# newbutton.net
KiCad netlist of a schematic drawn in EAGLE
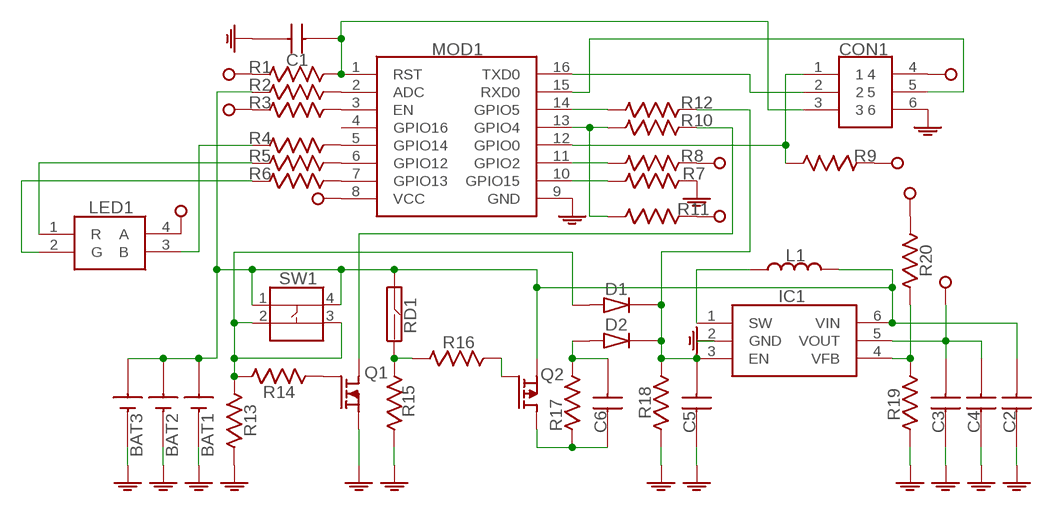
[diagram p0: schematic, sheet 1]

(export (version "E")
  (design (tool "Eeschema 10.0.6"))
  (components
    (comp (ref "BAT1")
      (value "AAA-CONTACTS")
      (footprint "eagle-import:AAA-CONTACTS")
      (libsource (lib "eagle-import") (part "AAA-CONTACTS"))
    )
    (comp (ref "BAT2")
      (value "AAA-CONTACTS")
      (footprint "eagle-import:AAA-CONTACTS")
      (libsource (lib "eagle-import") (part "AAA-CONTACTS"))
    )
    (comp (ref "BAT3")
      (value "AAA-CONTACTS")
      (footprint "eagle-import:AAA-CONTACTS")
      (libsource (lib "eagle-import") (part "AAA-CONTACTS"))
    )
    (comp (ref "C1")
      (value "CAPACITOR-0603")
      (footprint "eagle-import:0603")
      (libsource (lib "eagle-import") (part "CAPACITOR-0603"))
    )
    (comp (ref "C2")
      (value "CAPACITOR-0805")
      (footprint "eagle-import:0805")
      (libsource (lib "eagle-import") (part "CAPACITOR-0805"))
    )
    (comp (ref "C3")
      (value "CAPACITOR-0805")
      (footprint "eagle-import:0805")
      (libsource (lib "eagle-import") (part "CAPACITOR-0805"))
    )
    (comp (ref "C4")
      (value "CAPACITOR-0603")
      (footprint "eagle-import:0603")
      (libsource (lib "eagle-import") (part "CAPACITOR-0603"))
    )
    (comp (ref "C5")
      (value "CAPACITOR-0603")
      (footprint "eagle-import:0603")
      (libsource (lib "eagle-import") (part "CAPACITOR-0603"))
    )
    (comp (ref "C6")
      (value "CAPACITOR-0603")
      (footprint "eagle-import:0603")
      (libsource (lib "eagle-import") (part "CAPACITOR-0603"))
    )
    (comp (ref "CON1")
      (value "HEADER-6P-2R-DIP-2_54MM")
      (footprint "eagle-import:HEADER-6P-2R-DIP-2_54MM")
      (libsource (lib "eagle-import") (part "HEADER-6P-2R-DIP-2_54MM"))
    )
    (comp (ref "D1")
      (value "DIODE-0603")
      (footprint "eagle-import:0603-DIODE")
      (libsource (lib "eagle-import") (part "DIODE-0603"))
    )
    (comp (ref "D2")
      (value "DIODE-0603")
      (footprint "eagle-import:0603-DIODE")
      (libsource (lib "eagle-import") (part "DIODE-0603"))
    )
    (comp (ref "IC1")
      (value "MCP1640")
      (footprint "eagle-import:SOT23-6")
      (libsource (lib "eagle-import") (part "MCP1640"))
    )
    (comp (ref "L1")
      (value "INDUCTOR-0520-0630")
      (footprint "eagle-import:INDUCTOR-0520-0630")
      (libsource (lib "eagle-import") (part "INDUCTOR-0520-0630"))
    )
    (comp (ref "LED1")
      (value "LED-RGB-3528-PLCC4")
      (footprint "eagle-import:LED-RGB-3528-PLCC4")
      (libsource (lib "eagle-import") (part "LED-RGB-3528-PLCC4"))
    )
    (comp (ref "MOD1")
      (value "ESP-12S")
      (footprint "eagle-import:ESP-12S")
      (libsource (lib "eagle-import") (part "ESP-12S"))
    )
    (comp (ref "Q1")
      (value "N-MOSFET")
      (footprint "eagle-import:SOT23-3")
      (libsource (lib "eagle-import") (part "N-MOSFET"))
    )
    (comp (ref "Q2")
      (value "P-MOSFET")
      (footprint "eagle-import:SOT23-3")
      (libsource (lib "eagle-import") (part "P-MOSFET"))
    )
    (comp (ref "R1")
      (value "RESISTOR-0603")
      (footprint "eagle-import:0603")
      (libsource (lib "eagle-import") (part "RESISTOR-0603"))
    )
    (comp (ref "R2")
      (value "RESISTOR-0603")
      (footprint "eagle-import:0603")
      (libsource (lib "eagle-import") (part "RESISTOR-0603"))
    )
    (comp (ref "R3")
      (value "RESISTOR-0603")
      (footprint "eagle-import:0603")
      (libsource (lib "eagle-import") (part "RESISTOR-0603"))
    )
    (comp (ref "R4")
      (value "RESISTOR-0603")
      (footprint "eagle-import:0603")
      (libsource (lib "eagle-import") (part "RESISTOR-0603"))
    )
    (comp (ref "R5")
      (value "RESISTOR-0603")
      (footprint "eagle-import:0603")
      (libsource (lib "eagle-import") (part "RESISTOR-0603"))
    )
    (comp (ref "R6")
      (value "RESISTOR-0603")
      (footprint "eagle-import:0603")
      (libsource (lib "eagle-import") (part "RESISTOR-0603"))
    )
    (comp (ref "R7")
      (value "RESISTOR-0603")
      (footprint "eagle-import:0603")
      (libsource (lib "eagle-import") (part "RESISTOR-0603"))
    )
    (comp (ref "R8")
      (value "RESISTOR-0603")
      (footprint "eagle-import:0603")
      (libsource (lib "eagle-import") (part "RESISTOR-0603"))
    )
    (comp (ref "R9")
      (value "RESISTOR-0603")
      (footprint "eagle-import:0603")
      (libsource (lib "eagle-import") (part "RESISTOR-0603"))
    )
    (comp (ref "R10")
      (value "RESISTOR-0603")
      (footprint "eagle-import:0603")
      (libsource (lib "eagle-import") (part "RESISTOR-0603"))
    )
    (comp (ref "R11")
      (value "RESISTOR-0603")
      (footprint "eagle-import:0603")
      (libsource (lib "eagle-import") (part "RESISTOR-0603"))
    )
    (comp (ref "R12")
      (value "RESISTOR-0603")
      (footprint "eagle-import:0603")
      (libsource (lib "eagle-import") (part "RESISTOR-0603"))
    )
    (comp (ref "R13")
      (value "RESISTOR-0603")
      (footprint "eagle-import:0603")
      (libsource (lib "eagle-import") (part "RESISTOR-0603"))
    )
    (comp (ref "R14")
      (value "RESISTOR-0603")
      (footprint "eagle-import:0603")
      (libsource (lib "eagle-import") (part "RESISTOR-0603"))
    )
    (comp (ref "R15")
      (value "RESISTOR-0603")
      (footprint "eagle-import:0603")
      (libsource (lib "eagle-import") (part "RESISTOR-0603"))
    )
    (comp (ref "R16")
      (value "RESISTOR-0603")
      (footprint "eagle-import:0603")
      (libsource (lib "eagle-import") (part "RESISTOR-0603"))
    )
    (comp (ref "R17")
      (value "RESISTOR-0603")
      (footprint "eagle-import:0603")
      (libsource (lib "eagle-import") (part "RESISTOR-0603"))
    )
    (comp (ref "R18")
      (value "RESISTOR-0603")
      (footprint "eagle-import:0603")
      (libsource (lib "eagle-import") (part "RESISTOR-0603"))
    )
    (comp (ref "R19")
      (value "RESISTOR-0603")
      (footprint "eagle-import:0603")
      (libsource (lib "eagle-import") (part "RESISTOR-0603"))
    )
    (comp (ref "R20")
      (value "RESISTOR-0603")
      (footprint "eagle-import:0603")
      (libsource (lib "eagle-import") (part "RESISTOR-0603"))
    )
    (comp (ref "RD1")
      (value "REED-DIP")
      (footprint "eagle-import:REED-DIP")
      (libsource (lib "eagle-import") (part "REED-DIP"))
    )
    (comp (ref "SW1")
      (value "BUTTON-4P-SMD-5X5")
      (footprint "eagle-import:BUTTON-4P-SMD-5X5")
      (libsource (lib "eagle-import") (part "BUTTON-4P-SMD-5X5"))
    )
  )
  (nets
    (net (code "1") (name "GND") (class "Default")
      (node (ref "BAT1") (pin "2") (pinfunction "-_2") (pintype "power_in"))
      (node (ref "BAT1") (pin "4") (pinfunction "-_4") (pintype "power_in"))
      (node (ref "BAT2") (pin "2") (pinfunction "-_2") (pintype "power_in"))
      (node (ref "BAT2") (pin "4") (pinfunction "-_4") (pintype "power_in"))
      (node (ref "BAT3") (pin "2") (pinfunction "-_2") (pintype "power_in"))
      (node (ref "BAT3") (pin "4") (pinfunction "-_4") (pintype "power_in"))
      (node (ref "C1") (pin "1") (pinfunction "1_1") (pintype "passive"))
      (node (ref "C2") (pin "1") (pinfunction "1_1") (pintype "passive"))
      (node (ref "C3") (pin "1") (pinfunction "1_1") (pintype "passive"))
      (node (ref "C4") (pin "1") (pinfunction "1_1") (pintype "passive"))
      (node (ref "C5") (pin "1") (pinfunction "1_1") (pintype "passive"))
      (node (ref "CON1") (pin "6") (pinfunction "6_6") (pintype "bidirectional"))
      (node (ref "IC1") (pin "2") (pinfunction "GND_2") (pintype "power_in"))
      (node (ref "MOD1") (pin "9") (pinfunction "GND_9") (pintype "bidirectional"))
      (node (ref "Q1") (pin "2") (pinfunction "S_2") (pintype "bidirectional"))
      (node (ref "R13") (pin "1") (pinfunction "1_1") (pintype "passive"))
      (node (ref "R15") (pin "1") (pinfunction "1_1") (pintype "passive"))
      (node (ref "R18") (pin "1") (pinfunction "1_1") (pintype "passive"))
      (node (ref "R19") (pin "1") (pinfunction "1_1") (pintype "passive"))
      (node (ref "R7") (pin "2") (pinfunction "2_2") (pintype "passive"))
    )
    (net (code "2") (name "Net-(D1-A)") (class "Default")
      (node (ref "D1") (pin "1") (pinfunction "A_1") (pintype "bidirectional"))
      (node (ref "R13") (pin "2") (pinfunction "2_2") (pintype "passive"))
      (node (ref "R14") (pin "1") (pinfunction "1_1") (pintype "passive"))
      (node (ref "SW1") (pin "2") (pinfunction "2_2") (pintype "passive"))
      (node (ref "SW1") (pin "3") (pinfunction "3_3") (pintype "passive"))
    )
    (net (code "3") (name "Net-(D1-K)") (class "Default")
      (node (ref "C5") (pin "2") (pinfunction "2_2") (pintype "passive"))
      (node (ref "D1") (pin "2") (pinfunction "K_2") (pintype "bidirectional"))
      (node (ref "D2") (pin "2") (pinfunction "K_2") (pintype "bidirectional"))
      (node (ref "IC1") (pin "3") (pinfunction "EN_3") (pintype "bidirectional"))
      (node (ref "R12") (pin "2") (pinfunction "2_2") (pintype "passive"))
      (node (ref "R18") (pin "2") (pinfunction "2_2") (pintype "passive"))
    )
    (net (code "4") (name "Net-(D2-A)") (class "Default")
      (node (ref "C6") (pin "2") (pinfunction "2_2") (pintype "passive"))
      (node (ref "D2") (pin "1") (pinfunction "A_1") (pintype "bidirectional"))
      (node (ref "R17") (pin "2") (pinfunction "2_2") (pintype "passive"))
    )
    (net (code "5") (name "Net-(IC1-SW)") (class "Default")
      (node (ref "IC1") (pin "1") (pinfunction "SW_1") (pintype "power_in"))
      (node (ref "L1") (pin "1") (pinfunction "1_1") (pintype "passive"))
    )
    (net (code "6") (name "Net-(IC1-VFB)") (class "Default")
      (node (ref "IC1") (pin "4") (pinfunction "VFB_4") (pintype "bidirectional"))
      (node (ref "R19") (pin "2") (pinfunction "2_2") (pintype "passive"))
      (node (ref "R20") (pin "1") (pinfunction "1_1") (pintype "passive"))
    )
    (net (code "7") (name "Net-(IC1-VIN)") (class "Default")
      (node (ref "BAT1") (pin "1") (pinfunction "+_1") (pintype "power_in"))
      (node (ref "BAT1") (pin "3") (pinfunction "+_3") (pintype "power_in"))
      (node (ref "BAT2") (pin "1") (pinfunction "+_1") (pintype "power_in"))
      (node (ref "BAT2") (pin "3") (pinfunction "+_3") (pintype "power_in"))
      (node (ref "BAT3") (pin "1") (pinfunction "+_1") (pintype "power_in"))
      (node (ref "BAT3") (pin "3") (pinfunction "+_3") (pintype "power_in"))
      (node (ref "C2") (pin "2") (pinfunction "2_2") (pintype "passive"))
      (node (ref "IC1") (pin "6") (pinfunction "VIN_6") (pintype "power_in"))
      (node (ref "L1") (pin "2") (pinfunction "2_2") (pintype "passive"))
      (node (ref "Q2") (pin "2") (pinfunction "S_2") (pintype "bidirectional"))
      (node (ref "R2") (pin "1") (pinfunction "1_1") (pintype "passive"))
      (node (ref "RD1") (pin "P$1") (pinfunction "1_P$1") (pintype "passive"))
      (node (ref "SW1") (pin "1") (pinfunction "1_1") (pintype "passive"))
      (node (ref "SW1") (pin "4") (pinfunction "4_4") (pintype "passive"))
    )
    (net (code "8") (name "Net-(LED1-B)") (class "Default")
      (node (ref "LED1") (pin "3") (pinfunction "B_3") (pintype "bidirectional"))
      (node (ref "R4") (pin "1") (pinfunction "1_1") (pintype "passive"))
    )
    (net (code "9") (name "Net-(LED1-G)") (class "Default")
      (node (ref "LED1") (pin "2") (pinfunction "G_2") (pintype "bidirectional"))
      (node (ref "R6") (pin "1") (pinfunction "1_1") (pintype "passive"))
    )
    (net (code "10") (name "Net-(LED1-R)") (class "Default")
      (node (ref "LED1") (pin "1") (pinfunction "R_1") (pintype "bidirectional"))
      (node (ref "R5") (pin "1") (pinfunction "1_1") (pintype "passive"))
    )
    (net (code "11") (name "Net-(MOD1-ADC)") (class "Default")
      (node (ref "MOD1") (pin "2") (pinfunction "ADC_2") (pintype "bidirectional"))
      (node (ref "R2") (pin "2") (pinfunction "2_2") (pintype "passive"))
    )
    (net (code "12") (name "Net-(MOD1-EN)") (class "Default")
      (node (ref "MOD1") (pin "3") (pinfunction "EN_3") (pintype "bidirectional"))
      (node (ref "R3") (pin "2") (pinfunction "2_2") (pintype "passive"))
    )
    (net (code "13") (name "Net-(MOD1-GPIO0)") (class "Default")
      (node (ref "CON1") (pin "1") (pinfunction "1_1") (pintype "bidirectional"))
      (node (ref "MOD1") (pin "12") (pinfunction "GPIO0_12") (pintype "bidirectional"))
      (node (ref "R9") (pin "2") (pinfunction "2_2") (pintype "passive"))
    )
    (net (code "14") (name "Net-(MOD1-GPIO2)") (class "Default")
      (node (ref "MOD1") (pin "11") (pinfunction "GPIO2_11") (pintype "bidirectional"))
      (node (ref "R8") (pin "1") (pinfunction "1_1") (pintype "passive"))
    )
    (net (code "15") (name "Net-(MOD1-GPIO4)") (class "Default")
      (node (ref "MOD1") (pin "13") (pinfunction "GPIO4_13") (pintype "bidirectional"))
      (node (ref "R10") (pin "1") (pinfunction "1_1") (pintype "passive"))
      (node (ref "R11") (pin "1") (pinfunction "1_1") (pintype "passive"))
    )
    (net (code "16") (name "Net-(MOD1-GPIO5)") (class "Default")
      (node (ref "MOD1") (pin "14") (pinfunction "GPIO5_14") (pintype "bidirectional"))
      (node (ref "R12") (pin "1") (pinfunction "1_1") (pintype "passive"))
    )
    (net (code "17") (name "Net-(MOD1-GPIO12)") (class "Default")
      (node (ref "MOD1") (pin "6") (pinfunction "GPIO12_6") (pintype "bidirectional"))
      (node (ref "R5") (pin "2") (pinfunction "2_2") (pintype "passive"))
    )
    (net (code "18") (name "Net-(MOD1-GPIO13)") (class "Default")
      (node (ref "MOD1") (pin "7") (pinfunction "GPIO13_7") (pintype "bidirectional"))
      (node (ref "R6") (pin "2") (pinfunction "2_2") (pintype "passive"))
    )
    (net (code "19") (name "Net-(MOD1-GPIO14)") (class "Default")
      (node (ref "MOD1") (pin "5") (pinfunction "GPIO14_5") (pintype "bidirectional"))
      (node (ref "R4") (pin "2") (pinfunction "2_2") (pintype "passive"))
    )
    (net (code "20") (name "Net-(MOD1-GPIO15)") (class "Default")
      (node (ref "MOD1") (pin "10") (pinfunction "GPIO15_10") (pintype "bidirectional"))
      (node (ref "R7") (pin "1") (pinfunction "1_1") (pintype "passive"))
    )
    (net (code "21") (name "Net-(MOD1-RST)") (class "Default")
      (node (ref "C1") (pin "2") (pinfunction "2_2") (pintype "passive"))
      (node (ref "CON1") (pin "3") (pinfunction "3_3") (pintype "bidirectional"))
      (node (ref "MOD1") (pin "1") (pinfunction "RST_1") (pintype "bidirectional"))
      (node (ref "R1") (pin "2") (pinfunction "2_2") (pintype "passive"))
    )
    (net (code "22") (name "Net-(MOD1-RXD0)") (class "Default")
      (node (ref "CON1") (pin "5") (pinfunction "5_5") (pintype "bidirectional"))
      (node (ref "MOD1") (pin "15") (pinfunction "RXD0_15") (pintype "bidirectional"))
    )
    (net (code "23") (name "Net-(MOD1-TXD0)") (class "Default")
      (node (ref "CON1") (pin "2") (pinfunction "2_2") (pintype "bidirectional"))
      (node (ref "MOD1") (pin "16") (pinfunction "TXD0_16") (pintype "bidirectional"))
    )
    (net (code "24") (name "Net-(Q1-D)") (class "Default")
      (node (ref "Q1") (pin "3") (pinfunction "D_3") (pintype "bidirectional"))
      (node (ref "R10") (pin "2") (pinfunction "2_2") (pintype "passive"))
    )
    (net (code "25") (name "Net-(Q1-G)") (class "Default")
      (node (ref "Q1") (pin "1") (pinfunction "G_1") (pintype "bidirectional"))
      (node (ref "R14") (pin "2") (pinfunction "2_2") (pintype "passive"))
    )
    (net (code "26") (name "Net-(Q2-D)") (class "Default")
      (node (ref "C6") (pin "1") (pinfunction "1_1") (pintype "passive"))
      (node (ref "Q2") (pin "3") (pinfunction "D_3") (pintype "bidirectional"))
      (node (ref "R17") (pin "1") (pinfunction "1_1") (pintype "passive"))
    )
    (net (code "27") (name "Net-(Q2-G)") (class "Default")
      (node (ref "Q2") (pin "1") (pinfunction "G_1") (pintype "bidirectional"))
      (node (ref "R16") (pin "2") (pinfunction "2_2") (pintype "passive"))
    )
    (net (code "28") (name "Net-(RD1-2)") (class "Default")
      (node (ref "R15") (pin "2") (pinfunction "2_2") (pintype "passive"))
      (node (ref "R16") (pin "1") (pinfunction "1_1") (pintype "passive"))
      (node (ref "RD1") (pin "P$2") (pinfunction "2_P$2") (pintype "passive"))
    )
    (net (code "29") (name "VCC") (class "Default")
      (node (ref "C3") (pin "2") (pinfunction "2_2") (pintype "passive"))
      (node (ref "C4") (pin "2") (pinfunction "2_2") (pintype "passive"))
      (node (ref "CON1") (pin "4") (pinfunction "4_4") (pintype "bidirectional"))
      (node (ref "IC1") (pin "5") (pinfunction "VOUT_5") (pintype "power_in"))
      (node (ref "LED1") (pin "4") (pinfunction "A_4") (pintype "bidirectional"))
      (node (ref "MOD1") (pin "8") (pinfunction "VCC_8") (pintype "bidirectional"))
      (node (ref "R1") (pin "1") (pinfunction "1_1") (pintype "passive"))
      (node (ref "R11") (pin "2") (pinfunction "2_2") (pintype "passive"))
      (node (ref "R20") (pin "2") (pinfunction "2_2") (pintype "passive"))
      (node (ref "R3") (pin "1") (pinfunction "1_1") (pintype "passive"))
      (node (ref "R8") (pin "2") (pinfunction "2_2") (pintype "passive"))
      (node (ref "R9") (pin "1") (pinfunction "1_1") (pintype "passive"))
    )
    (net (code "30") (name "unconnected-(MOD1-GPIO16-Pad4)") (class "Default")
      (node (ref "MOD1") (pin "4") (pinfunction "GPIO16_4") (pintype "bidirectional"))
    )
  )
)
